# 1_ADSTM32-Power.net
KiCad netlist of a schematic drawn in Altium Designer
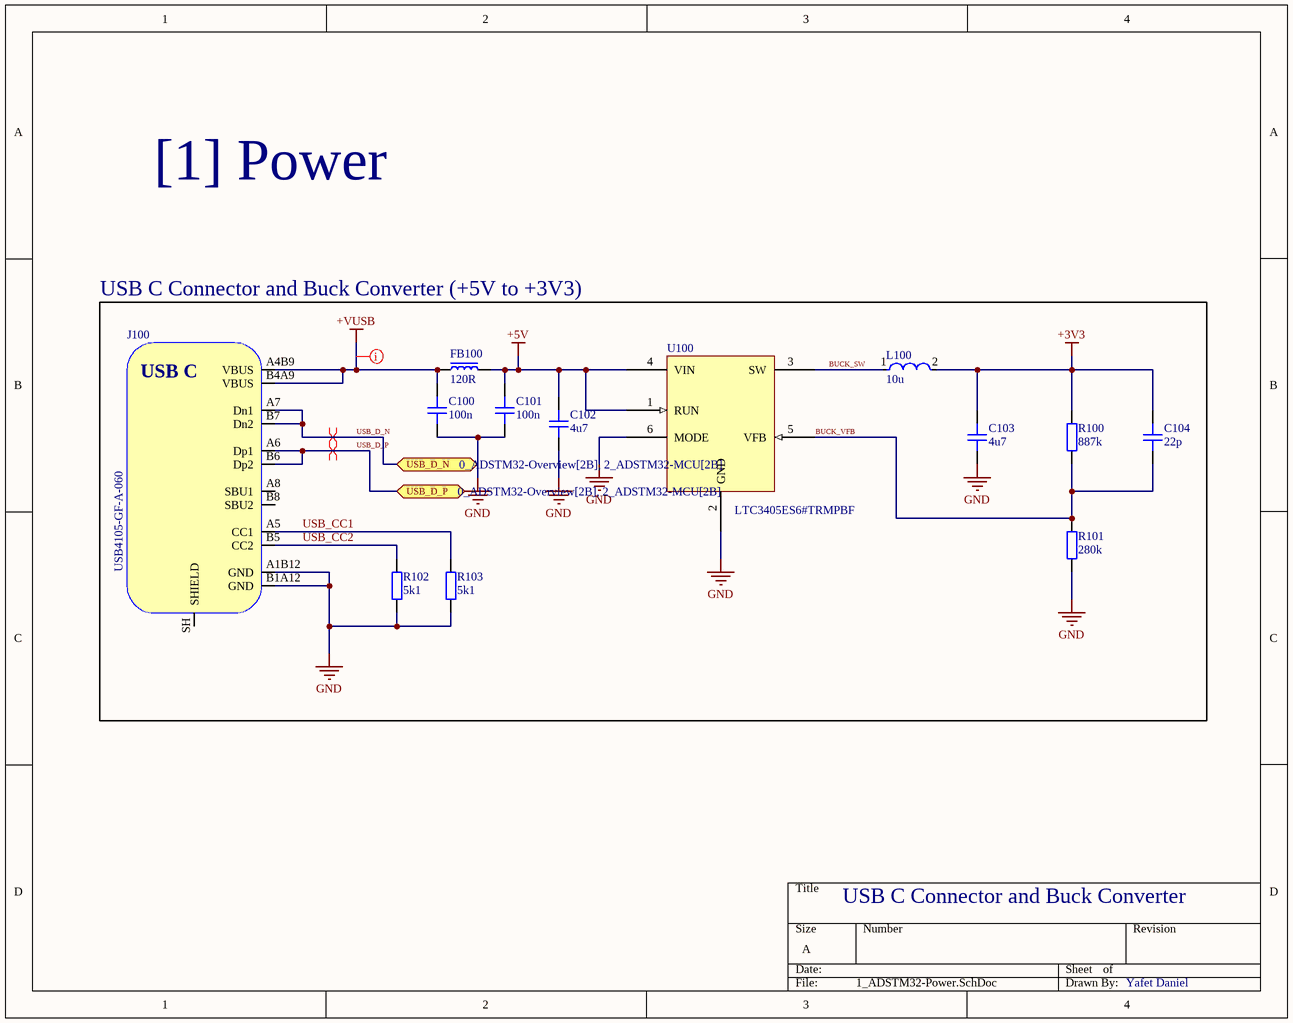
[diagram p0: 1_ADSTM32-Power.SchDoc]

(export (version "E")
  (design (tool "Eeschema 10.0.6"))
  (components
    (comp (ref "C100")
      (value "100n")
      (footprint "CAP_0603")
      (description "Capacitor SMD 0603")
      (libsource (lib "Schematic-Lib-PhilsLab") (part "CAP_0603"))
    )
    (comp (ref "C101")
      (value "100n")
      (footprint "CAP_0603")
      (description "Capacitor SMD 0603")
      (libsource (lib "Schematic-Lib-PhilsLab") (part "CAP_0603"))
    )
    (comp (ref "C102")
      (value "4u7")
      (footprint "CAP_0805")
      (description "Capacitor SMD 0805")
      (libsource (lib "Schematic-Lib-PhilsLab") (part "CAP_0805"))
    )
    (comp (ref "C103")
      (value "4u7")
      (footprint "CAP_0805")
      (description "Capacitor SMD 0805")
      (libsource (lib "Schematic-Lib-PhilsLab") (part "CAP_0805"))
    )
    (comp (ref "C104")
      (value "22p")
      (footprint "CAP_0603")
      (description "Capacitor SMD 0603")
      (libsource (lib "Schematic-Lib-PhilsLab") (part "CAP_0603"))
    )
    (comp (ref "FB100")
      (value "120R")
      (footprint "FB_0402")
      (description "Ferrite Bead SMD 0402")
      (libsource (lib "Schematic-Lib-PhilsLab") (part "FB_0402"))
    )
    (comp (ref "J100")
      (value "USB4105-GF-A-060")
      (footprint "USB4105-GF-A-060")
      (description "USB Connector Type C SMT 12 Pin")
      (fields (field (name "MANUFACTURER") "GCT"))
      (libsource (lib "Schematic-Lib-PhilsLab") (part "USB4105-GF-A-060"))
    )
    (comp (ref "L100")
      (value "10u")
      (footprint "FP-NRH2412-MFG")
      (description "Shielded Wirewound Inductor 10uH 20% 0.51A 0.72Ω SMD")
      (fields (field (name "TOLERANCE") "20%"))
      (libsource (lib "Altium Content Vault") (part "725321dda6339637d4d059423bc1c3c"))
    )
    (comp (ref "R100")
      (value "887k")
      (footprint "RES_0603")
      (description "Resistor SMD 0603")
      (libsource (lib "Schematic-Lib-PhilsLab") (part "RES_0603"))
    )
    (comp (ref "R101")
      (value "280k")
      (footprint "RES_0603")
      (description "Resistor SMD 0603")
      (libsource (lib "Schematic-Lib-PhilsLab") (part "RES_0603"))
    )
    (comp (ref "R102")
      (value "5k1")
      (footprint "RES_0603")
      (description "Resistor SMD 0603")
      (libsource (lib "Schematic-Lib-PhilsLab") (part "RES_0603"))
    )
    (comp (ref "R103")
      (value "5k1")
      (footprint "RES_0603")
      (description "Resistor SMD 0603")
      (libsource (lib "Schematic-Lib-PhilsLab") (part "RES_0603"))
    )
    (comp (ref "U100")
      (value "LTC3405ES6#TRMPBF")
      (footprint "SOT-23-6")
      (description "1.5MHz, 300mA\r\n Synchronous Step-Down\r\n Regulator in ThinSOT")
      (fields (field (name "MANUFACTURER") "Analog Devices"))
      (libsource (lib "Schematic-Lib-PhilsLab") (part "LTC3405ES6#TRMPBF"))
    )
  )
  (nets
    (net (code "1") (name "+3V3") (class "Default")
      (node (ref "C103") (pin "2") (pinfunction "2_2") (pintype "passive"))
      (node (ref "C104") (pin "2") (pinfunction "2_2") (pintype "passive"))
      (node (ref "L100") (pin "2") (pinfunction "2_2") (pintype "passive"))
      (node (ref "R100") (pin "2") (pinfunction "2_2") (pintype "passive"))
    )
    (net (code "2") (name "+5V") (class "Default")
      (node (ref "C101") (pin "2") (pinfunction "2_2") (pintype "passive"))
      (node (ref "C102") (pin "2") (pinfunction "2_2") (pintype "passive"))
      (node (ref "FB100") (pin "2") (pinfunction "2_2") (pintype "passive"))
      (node (ref "U100") (pin "1") (pinfunction "RUN_1") (pintype "input"))
      (node (ref "U100") (pin "4") (pinfunction "VIN_4") (pintype "power_in"))
    )
    (net (code "3") (name "+VUSB") (class "Default")
      (node (ref "C100") (pin "2") (pinfunction "2_2") (pintype "passive"))
      (node (ref "FB100") (pin "1") (pinfunction "1_1") (pintype "passive"))
      (node (ref "J100") (pin "A4B9") (pinfunction "VBUS_A4B9") (pintype "passive"))
      (node (ref "J100") (pin "B4A9") (pinfunction "VBUS_B4A9") (pintype "passive"))
    )
    (net (code "4") (name "/BUCK_SW") (class "Default")
      (node (ref "L100") (pin "1") (pinfunction "1_1") (pintype "passive"))
      (node (ref "U100") (pin "3") (pinfunction "SW_3") (pintype "power_in"))
    )
    (net (code "5") (name "/BUCK_VFB") (class "Default")
      (node (ref "C104") (pin "1") (pinfunction "1_1") (pintype "passive"))
      (node (ref "R100") (pin "1") (pinfunction "1_1") (pintype "passive"))
      (node (ref "R101") (pin "2") (pinfunction "2_2") (pintype "passive"))
      (node (ref "U100") (pin "5") (pinfunction "VFB_5") (pintype "input"))
    )
    (net (code "6") (name "/USB_CC1") (class "Default")
      (node (ref "J100") (pin "A5") (pinfunction "CC1_A5") (pintype "passive"))
      (node (ref "R103") (pin "2") (pinfunction "2_2") (pintype "passive"))
    )
    (net (code "7") (name "/USB_CC2") (class "Default")
      (node (ref "J100") (pin "B5") (pinfunction "CC2_B5") (pintype "passive"))
      (node (ref "R102") (pin "2") (pinfunction "2_2") (pintype "passive"))
    )
    (net (code "8") (name "/USB_D_N") (class "Default")
      (node (ref "J100") (pin "A7") (pinfunction "Dn1_A7") (pintype "passive"))
      (node (ref "J100") (pin "B7") (pinfunction "Dn2_B7") (pintype "passive"))
    )
    (net (code "9") (name "/USB_D_P") (class "Default")
      (node (ref "J100") (pin "A6") (pinfunction "Dp1_A6") (pintype "passive"))
      (node (ref "J100") (pin "B6") (pinfunction "Dp2_B6") (pintype "passive"))
    )
    (net (code "10") (name "GND") (class "Default")
      (node (ref "C100") (pin "1") (pinfunction "1_1") (pintype "passive"))
      (node (ref "C101") (pin "1") (pinfunction "1_1") (pintype "passive"))
      (node (ref "C102") (pin "1") (pinfunction "1_1") (pintype "passive"))
      (node (ref "C103") (pin "1") (pinfunction "1_1") (pintype "passive"))
      (node (ref "J100") (pin "A1B12") (pinfunction "GND_A1B12") (pintype "passive"))
      (node (ref "J100") (pin "B1A12") (pinfunction "GND_B1A12") (pintype "passive"))
      (node (ref "R101") (pin "1") (pinfunction "1_1") (pintype "passive"))
      (node (ref "R102") (pin "1") (pinfunction "1_1") (pintype "passive"))
      (node (ref "R103") (pin "1") (pinfunction "1_1") (pintype "passive"))
      (node (ref "U100") (pin "2") (pinfunction "GND_2") (pintype "power_in"))
      (node (ref "U100") (pin "6") (pinfunction "MODE_6") (pintype "passive"))
    )
    (net (code "11") (name "unconnected-(J100-SBU1-PadA8)") (class "Default")
      (node (ref "J100") (pin "A8") (pinfunction "SBU1_A8") (pintype "passive"))
    )
    (net (code "12") (name "unconnected-(J100-SBU2-PadB8)") (class "Default")
      (node (ref "J100") (pin "B8") (pinfunction "SBU2_B8") (pintype "passive"))
    )
    (net (code "13") (name "unconnected-(J100-SHIELD-PadSH)") (class "Default")
      (node (ref "J100") (pin "SH") (pinfunction "SHIELD_SH") (pintype "passive"))
    )
  )
)
